# ILI9342_BREAKOUT.net
KiCad netlist of a schematic drawn in EAGLE
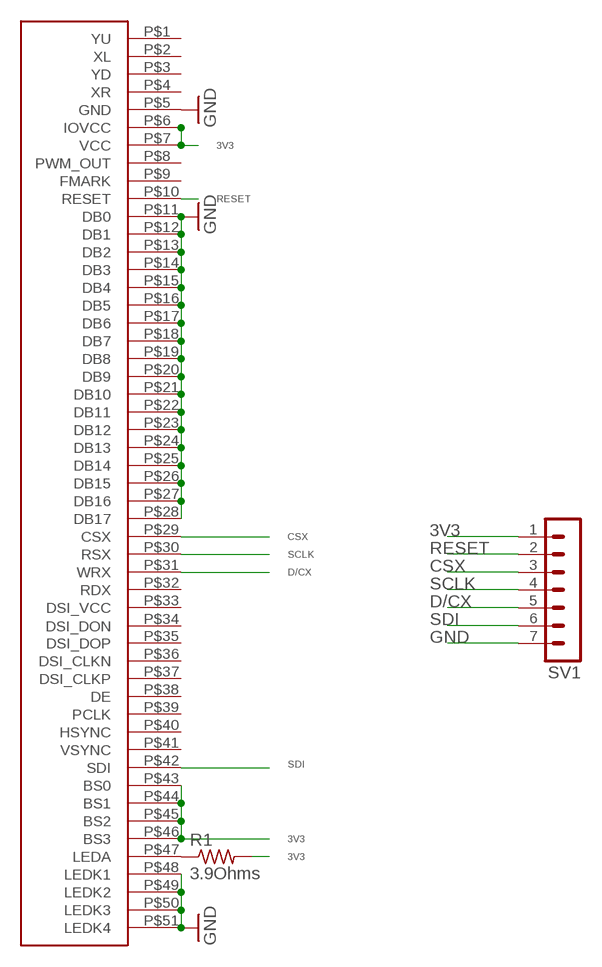
[diagram p0: schematic, sheet 1]

(export (version "E")
  (design (tool "Eeschema 10.0.6"))
  (components
    (comp (ref "2.6ILI9342")
      (value "TFT-DISPLAY-2.6-51PIN")
      (footprint "eagle-import:TFT-DISPLAY-2.6-51PIN")
      (libsource (lib "eagle-import") (part "TFT-DISPLAY-2.6-51PIN"))
    )
    (comp (ref "R1")
      (value "3.9Ohms")
      (footprint "eagle-import:R0805")
      (libsource (lib "eagle-import") (part "R-US_R0805"))
    )
    (comp (ref "SV1")
      (value "MA07-1")
      (footprint "eagle-import:MA07-1")
      (libsource (lib "eagle-import") (part "MA07-1"))
    )
  )
  (nets
    (net (code "1") (name "/3V3") (class "Default")
      (node (ref "2.6ILI9342") (pin "P$43") (pinfunction "BS0_P$43") (pintype "bidirectional"))
      (node (ref "2.6ILI9342") (pin "P$44") (pinfunction "BS1_P$44") (pintype "bidirectional"))
      (node (ref "2.6ILI9342") (pin "P$45") (pinfunction "BS2_P$45") (pintype "bidirectional"))
      (node (ref "2.6ILI9342") (pin "P$46") (pinfunction "BS3_P$46") (pintype "bidirectional"))
      (node (ref "2.6ILI9342") (pin "P$6") (pinfunction "IOVCC_P$6") (pintype "bidirectional"))
      (node (ref "2.6ILI9342") (pin "P$7") (pinfunction "VCC_P$7") (pintype "bidirectional"))
      (node (ref "R1") (pin "2") (pinfunction "2_2") (pintype "passive"))
      (node (ref "SV1") (pin "1") (pinfunction "1_1") (pintype "passive"))
    )
    (net (code "2") (name "/CSX") (class "Default")
      (node (ref "2.6ILI9342") (pin "P$29") (pinfunction "CSX_P$29") (pintype "bidirectional"))
      (node (ref "SV1") (pin "3") (pinfunction "3_3") (pintype "passive"))
    )
    (net (code "3") (name "/D{slash}CX") (class "Default")
      (node (ref "2.6ILI9342") (pin "P$31") (pinfunction "WRX_P$31") (pintype "bidirectional"))
      (node (ref "SV1") (pin "5") (pinfunction "5_5") (pintype "passive"))
    )
    (net (code "4") (name "/RESET") (class "Default")
      (node (ref "2.6ILI9342") (pin "P$10") (pinfunction "RESET_P$10") (pintype "bidirectional"))
      (node (ref "SV1") (pin "2") (pinfunction "2_2") (pintype "passive"))
    )
    (net (code "5") (name "/SCLK") (class "Default")
      (node (ref "2.6ILI9342") (pin "P$30") (pinfunction "RSX_P$30") (pintype "bidirectional"))
      (node (ref "SV1") (pin "4") (pinfunction "4_4") (pintype "passive"))
    )
    (net (code "6") (name "/SDI") (class "Default")
      (node (ref "2.6ILI9342") (pin "P$42") (pinfunction "SDI_P$42") (pintype "bidirectional"))
      (node (ref "SV1") (pin "6") (pinfunction "6_6") (pintype "passive"))
    )
    (net (code "7") (name "GND") (class "Default")
      (node (ref "2.6ILI9342") (pin "P$11") (pinfunction "DB0_P$11") (pintype "bidirectional"))
      (node (ref "2.6ILI9342") (pin "P$12") (pinfunction "DB1_P$12") (pintype "bidirectional"))
      (node (ref "2.6ILI9342") (pin "P$13") (pinfunction "DB2_P$13") (pintype "bidirectional"))
      (node (ref "2.6ILI9342") (pin "P$14") (pinfunction "DB3_P$14") (pintype "bidirectional"))
      (node (ref "2.6ILI9342") (pin "P$15") (pinfunction "DB4_P$15") (pintype "bidirectional"))
      (node (ref "2.6ILI9342") (pin "P$16") (pinfunction "DB5_P$16") (pintype "bidirectional"))
      (node (ref "2.6ILI9342") (pin "P$17") (pinfunction "DB6_P$17") (pintype "bidirectional"))
      (node (ref "2.6ILI9342") (pin "P$18") (pinfunction "DB7_P$18") (pintype "bidirectional"))
      (node (ref "2.6ILI9342") (pin "P$19") (pinfunction "DB8_P$19") (pintype "bidirectional"))
      (node (ref "2.6ILI9342") (pin "P$20") (pinfunction "DB9_P$20") (pintype "bidirectional"))
      (node (ref "2.6ILI9342") (pin "P$21") (pinfunction "DB10_P$21") (pintype "bidirectional"))
      (node (ref "2.6ILI9342") (pin "P$22") (pinfunction "DB11_P$22") (pintype "bidirectional"))
      (node (ref "2.6ILI9342") (pin "P$23") (pinfunction "DB12_P$23") (pintype "bidirectional"))
      (node (ref "2.6ILI9342") (pin "P$24") (pinfunction "DB13_P$24") (pintype "bidirectional"))
      (node (ref "2.6ILI9342") (pin "P$25") (pinfunction "DB14_P$25") (pintype "bidirectional"))
      (node (ref "2.6ILI9342") (pin "P$26") (pinfunction "DB15_P$26") (pintype "bidirectional"))
      (node (ref "2.6ILI9342") (pin "P$27") (pinfunction "DB16_P$27") (pintype "bidirectional"))
      (node (ref "2.6ILI9342") (pin "P$28") (pinfunction "DB17_P$28") (pintype "bidirectional"))
      (node (ref "2.6ILI9342") (pin "P$48") (pinfunction "LEDK1_P$48") (pintype "bidirectional"))
      (node (ref "2.6ILI9342") (pin "P$49") (pinfunction "LEDK2_P$49") (pintype "bidirectional"))
      (node (ref "2.6ILI9342") (pin "P$5") (pinfunction "GND_P$5") (pintype "bidirectional"))
      (node (ref "2.6ILI9342") (pin "P$50") (pinfunction "LEDK3_P$50") (pintype "bidirectional"))
      (node (ref "2.6ILI9342") (pin "P$51") (pinfunction "LEDK4_P$51") (pintype "bidirectional"))
      (node (ref "SV1") (pin "7") (pinfunction "7_7") (pintype "passive"))
    )
    (net (code "8") (name "Net-(2.6ILI9342-LEDA)") (class "Default")
      (node (ref "2.6ILI9342") (pin "P$47") (pinfunction "LEDA_P$47") (pintype "bidirectional"))
      (node (ref "R1") (pin "1") (pinfunction "1_1") (pintype "passive"))
    )
    (net (code "9") (name "unconnected-(2.6ILI9342-DE-PadP$38)") (class "Default")
      (node (ref "2.6ILI9342") (pin "P$38") (pinfunction "DE_P$38") (pintype "bidirectional"))
    )
    (net (code "10") (name "unconnected-(2.6ILI9342-DSI_CLKN-PadP$36)") (class "Default")
      (node (ref "2.6ILI9342") (pin "P$36") (pinfunction "DSI_CLKN_P$36") (pintype "bidirectional"))
    )
    (net (code "11") (name "unconnected-(2.6ILI9342-DSI_CLKP-PadP$37)") (class "Default")
      (node (ref "2.6ILI9342") (pin "P$37") (pinfunction "DSI_CLKP_P$37") (pintype "bidirectional"))
    )
    (net (code "12") (name "unconnected-(2.6ILI9342-DSI_DON-PadP$34)") (class "Default")
      (node (ref "2.6ILI9342") (pin "P$34") (pinfunction "DSI_DON_P$34") (pintype "bidirectional"))
    )
    (net (code "13") (name "unconnected-(2.6ILI9342-DSI_DOP-PadP$35)") (class "Default")
      (node (ref "2.6ILI9342") (pin "P$35") (pinfunction "DSI_DOP_P$35") (pintype "bidirectional"))
    )
    (net (code "14") (name "unconnected-(2.6ILI9342-DSI_VCC-PadP$33)") (class "Default")
      (node (ref "2.6ILI9342") (pin "P$33") (pinfunction "DSI_VCC_P$33") (pintype "bidirectional"))
    )
    (net (code "15") (name "unconnected-(2.6ILI9342-FMARK-PadP$9)") (class "Default")
      (node (ref "2.6ILI9342") (pin "P$9") (pinfunction "FMARK_P$9") (pintype "bidirectional"))
    )
    (net (code "16") (name "unconnected-(2.6ILI9342-HSYNC-PadP$40)") (class "Default")
      (node (ref "2.6ILI9342") (pin "P$40") (pinfunction "HSYNC_P$40") (pintype "bidirectional"))
    )
    (net (code "17") (name "unconnected-(2.6ILI9342-PCLK-PadP$39)") (class "Default")
      (node (ref "2.6ILI9342") (pin "P$39") (pinfunction "PCLK_P$39") (pintype "bidirectional"))
    )
    (net (code "18") (name "unconnected-(2.6ILI9342-PWM_OUT-PadP$8)") (class "Default")
      (node (ref "2.6ILI9342") (pin "P$8") (pinfunction "PWM_OUT_P$8") (pintype "bidirectional"))
    )
    (net (code "19") (name "unconnected-(2.6ILI9342-RDX-PadP$32)") (class "Default")
      (node (ref "2.6ILI9342") (pin "P$32") (pinfunction "RDX_P$32") (pintype "bidirectional"))
    )
    (net (code "20") (name "unconnected-(2.6ILI9342-VSYNC-PadP$41)") (class "Default")
      (node (ref "2.6ILI9342") (pin "P$41") (pinfunction "VSYNC_P$41") (pintype "bidirectional"))
    )
    (net (code "21") (name "unconnected-(2.6ILI9342-XL-PadP$2)") (class "Default")
      (node (ref "2.6ILI9342") (pin "P$2") (pinfunction "XL_P$2") (pintype "bidirectional"))
    )
    (net (code "22") (name "unconnected-(2.6ILI9342-XR-PadP$4)") (class "Default")
      (node (ref "2.6ILI9342") (pin "P$4") (pinfunction "XR_P$4") (pintype "bidirectional"))
    )
    (net (code "23") (name "unconnected-(2.6ILI9342-YD-PadP$3)") (class "Default")
      (node (ref "2.6ILI9342") (pin "P$3") (pinfunction "YD_P$3") (pintype "bidirectional"))
    )
    (net (code "24") (name "unconnected-(2.6ILI9342-YU-PadP$1)") (class "Default")
      (node (ref "2.6ILI9342") (pin "P$1") (pinfunction "YU_P$1") (pintype "bidirectional"))
    )
  )
)
